# usb_conn.net
KiCad netlist of a schematic drawn in Altium Designer
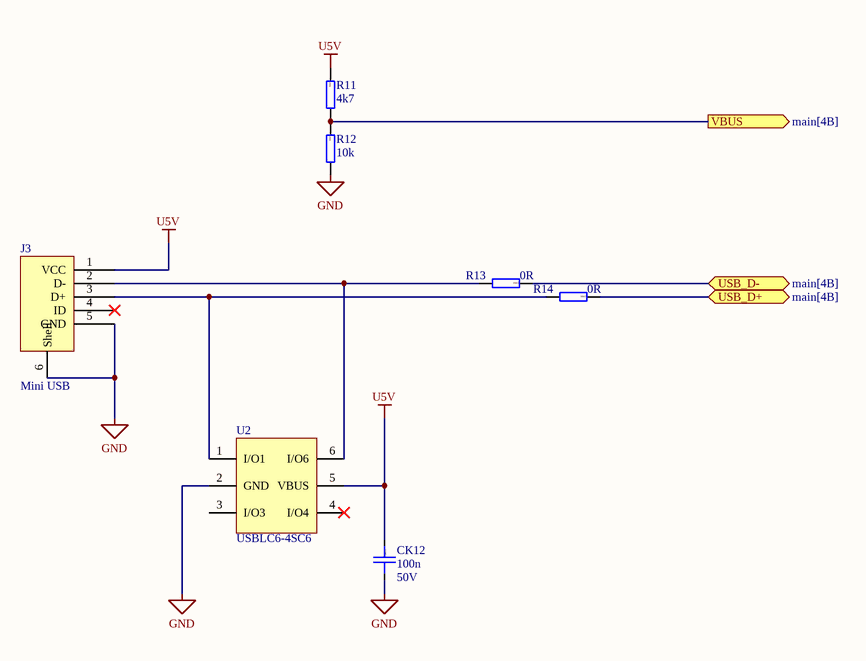
[diagram p0: usb_conn.SchDoc]

(export (version "E")
  (design (tool "Eeschema 10.0.6"))
  (components
    (comp (ref "CK12")
      (value "100n")
      (footprint "CAP0603")
      (description "50V 100nF X7R ±10% 0603 Multilayer Ceramic Capacitors MLCC - SMD/SMT ROHS")
      (fields (field (name "JLCPCB PART") "C14663") (field (name "VOLTAGE RATING") "50V"))
      (libsource (lib "Kubikova ultra knihovna") (part "Cap 100n 0603"))
    )
    (comp (ref "J3")
      (value "Mini USB")
      (footprint "USB B Mini horizontal")
      (description "Konektor: USB B mini; zásuvka; na PCB; SMT; PIN: 5; vodorovné")
      (fields (field (name "TME PART") "MX-67503-1020"))
      (libsource (lib "Kubikova ultra knihovna") (part "Mini USB"))
    )
    (comp (ref "R11")
      (value "4k7")
      (footprint "RESC2012X06N(SMR0805)")
      (description "125mW Thick Film Resistors 150V ±100ppm/℃ ±1% 4.7kΩ 0805 Chip Resistor - Surface Mount ROHS")
      (fields (field (name "JLCPCB PART") "C17673") (field (name "AUTHOR") "JP/27.03.2014"))
      (libsource (lib "Kubikova ultra knihovna") (part "Res 4k7 0805"))
    )
    (comp (ref "R12")
      (value "10k")
      (footprint "RESC2012X06N(SMR0805)")
      (description "125mW Thick Film Resistors 150V ±100ppm/℃ ±1% 10kΩ 0805 Chip Resistor - Surface Mount ROHS")
      (fields (field (name "JLCPCB PART") "C17414"))
      (libsource (lib "Kubikova ultra knihovna") (part "Res 10k 0805"))
    )
    (comp (ref "R13")
      (value "0R")
      (footprint "RESC2012X06N(SMR0805)")
      (description "125mW Thick Film Resistors 150V ±800ppm/℃ ±1% 0Ω 0805 Chip Resistor - Surface Mount ROHS")
      (fields (field (name "JLCPCB PART") "C17477") (field (name "AUTHOR") "JP/27.03.2014"))
      (libsource (lib "Kubikova ultra knihovna") (part "Res 0R 0805"))
    )
    (comp (ref "R14")
      (value "0R")
      (footprint "RESC2012X06N(SMR0805)")
      (description "125mW Thick Film Resistors 150V ±800ppm/℃ ±1% 0Ω 0805 Chip Resistor - Surface Mount ROHS")
      (fields (field (name "JLCPCB PART") "C17477") (field (name "AUTHOR") "JP/27.03.2014"))
      (libsource (lib "Kubikova ultra knihovna") (part "Res 0R 0805"))
    )
    (comp (ref "U2")
      (value "USBLC6-4SC6")
      (footprint "SOT23-6")
      (description "5A 17V 6V Unidirectional 5.25V SOT-23-6 ESD and Surge Protection (TVS/ESD) ROHS")
      (fields (field (name "JLCPCB PART") "C111212"))
      (libsource (lib "Kubikova ultra knihovna") (part "USBLC6-4SC6"))
    )
  )
  (nets
    (net (code "1") (name "/USB_D+") (class "Default")
      (node (ref "R14") (pin "2") (pinfunction "2_2") (pintype "passive"))
    )
    (net (code "2") (name "/USB_D-") (class "Default")
      (node (ref "R13") (pin "2") (pinfunction "2_2") (pintype "passive"))
    )
    (net (code "3") (name "/VBUS") (class "Default")
      (node (ref "R11") (pin "1") (pinfunction "1_1") (pintype "passive"))
      (node (ref "R12") (pin "2") (pinfunction "2_2") (pintype "passive"))
    )
    (net (code "4") (name "GND") (class "Default")
      (node (ref "CK12") (pin "2") (pinfunction "2_2") (pintype "passive"))
      (node (ref "J3") (pin "5") (pinfunction "GND_5") (pintype "passive"))
      (node (ref "J3") (pin "6") (pinfunction "Shell_6") (pintype "passive"))
      (node (ref "R12") (pin "1") (pinfunction "1_1") (pintype "passive"))
      (node (ref "U2") (pin "2") (pinfunction "GND_2") (pintype "passive"))
    )
    (net (code "5") (name "Net-(J3-D+)") (class "Default")
      (node (ref "J3") (pin "3") (pinfunction "D+_3") (pintype "passive"))
      (node (ref "R14") (pin "1") (pinfunction "1_1") (pintype "passive"))
      (node (ref "U2") (pin "1") (pinfunction "I/O1_1") (pintype "passive"))
    )
    (net (code "6") (name "Net-(J3-D-)") (class "Default")
      (node (ref "J3") (pin "2") (pinfunction "D-_2") (pintype "passive"))
      (node (ref "R13") (pin "1") (pinfunction "1_1") (pintype "passive"))
      (node (ref "U2") (pin "6") (pinfunction "I/O6_6") (pintype "passive"))
    )
    (net (code "7") (name "U5V") (class "Default")
      (node (ref "CK12") (pin "1") (pinfunction "1_1") (pintype "passive"))
      (node (ref "J3") (pin "1") (pinfunction "VCC_1") (pintype "passive"))
      (node (ref "R11") (pin "2") (pinfunction "2_2") (pintype "passive"))
      (node (ref "U2") (pin "5") (pinfunction "VBUS_5") (pintype "passive"))
    )
    (net (code "8") (name "unconnected-(J3-ID-Pad4)") (class "Default")
      (node (ref "J3") (pin "4") (pinfunction "ID_4") (pintype "passive+no_connect"))
    )
    (net (code "9") (name "unconnected-(U2-I{slash}O3-Pad3)") (class "Default")
      (node (ref "U2") (pin "3") (pinfunction "I/O3_3") (pintype "passive"))
    )
    (net (code "10") (name "unconnected-(U2-I{slash}O4-Pad4)") (class "Default")
      (node (ref "U2") (pin "4") (pinfunction "I/O4_4") (pintype "passive+no_connect"))
    )
  )
)
